# Top_Sheet.net
KiCad netlist of a schematic drawn in Altium Designer
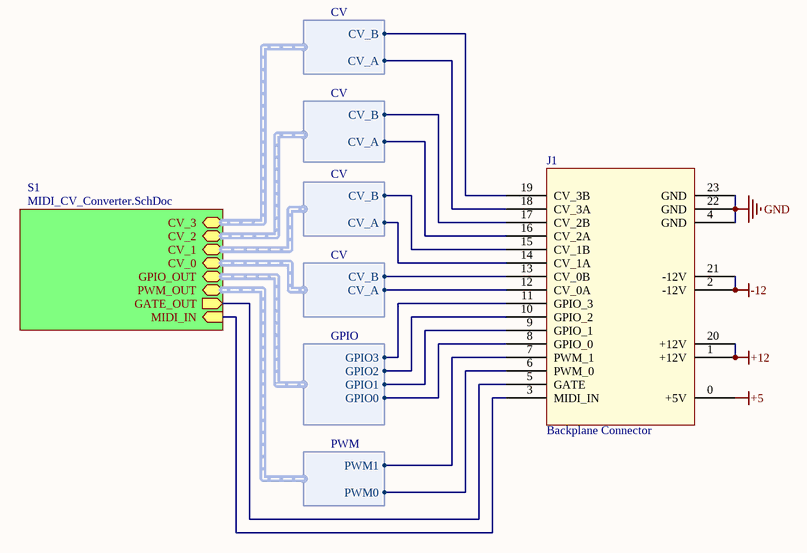
[diagram p0: Top Sheet.SchDoc]

(export (version "E")
  (design (tool "Eeschema 10.0.6"))
  (components
    (comp (ref "J1")
      (value "Backplane Connector")
      (footprint "MIDI-CV CONVERTER MODULE")
      (libsource (lib "Gary_Module") (part "MIDI_CV_Converter"))
    )
  )
  (nets
    (net (code "4") (name "+5") (class "Default")
      (node (ref "J1") (pin "0") (pinfunction "+5V_0") (pintype "passive"))
    )
    (net (code "5") (name "+12") (class "Default")
      (node (ref "J1") (pin "1") (pinfunction "+12V_1") (pintype "passive"))
      (node (ref "J1") (pin "20") (pinfunction "+12V_20") (pintype "passive"))
    )
    (net (code "6") (name "-12") (class "Default")
      (node (ref "J1") (pin "2") (pinfunction "-12V_2") (pintype "passive"))
      (node (ref "J1") (pin "21") (pinfunction "-12V_21") (pintype "passive"))
    )
    (net (code "7") (name "/GATE_OUT") (class "Default")
      (node (ref "J1") (pin "5") (pinfunction "GATE_5") (pintype "passive"))
    )
    (net (code "8") (name "/GPIO0") (class "Default")
      (node (ref "J1") (pin "8") (pinfunction "GPIO_0_8") (pintype "passive"))
    )
    (net (code "9") (name "/GPIO1") (class "Default")
      (node (ref "J1") (pin "9") (pinfunction "GPIO_1_9") (pintype "passive"))
    )
    (net (code "10") (name "/GPIO2") (class "Default")
      (node (ref "J1") (pin "10") (pinfunction "GPIO_2_10") (pintype "passive"))
    )
    (net (code "11") (name "/GPIO3") (class "Default")
      (node (ref "J1") (pin "11") (pinfunction "GPIO_3_11") (pintype "passive"))
    )
    (net (code "12") (name "/MIDI_IN") (class "Default")
      (node (ref "J1") (pin "3") (pinfunction "MIDI_IN_3") (pintype "passive"))
    )
    (net (code "13") (name "/PWM0") (class "Default")
      (node (ref "J1") (pin "6") (pinfunction "PWM_0_6") (pintype "passive"))
    )
    (net (code "14") (name "/PWM1") (class "Default")
      (node (ref "J1") (pin "7") (pinfunction "PWM_1_7") (pintype "passive"))
    )
    (net (code "18") (name "GND") (class "Default")
      (node (ref "J1") (pin "22") (pinfunction "GND_22") (pintype "passive"))
      (node (ref "J1") (pin "23") (pinfunction "GND_23") (pintype "passive"))
      (node (ref "J1") (pin "4") (pinfunction "GND_4") (pintype "passive"))
    )
    (net (code "19") (name "unconnected-(J1-CV_0A-Pad12)") (class "Default")
      (node (ref "J1") (pin "12") (pinfunction "CV_0A_12") (pintype "passive"))
    )
    (net (code "20") (name "unconnected-(J1-CV_0B-Pad13)") (class "Default")
      (node (ref "J1") (pin "13") (pinfunction "CV_0B_13") (pintype "passive"))
    )
    (net (code "21") (name "unconnected-(J1-CV_1A-Pad14)") (class "Default")
      (node (ref "J1") (pin "14") (pinfunction "CV_1A_14") (pintype "passive"))
    )
    (net (code "22") (name "unconnected-(J1-CV_1B-Pad15)") (class "Default")
      (node (ref "J1") (pin "15") (pinfunction "CV_1B_15") (pintype "passive"))
    )
    (net (code "23") (name "unconnected-(J1-CV_2A-Pad16)") (class "Default")
      (node (ref "J1") (pin "16") (pinfunction "CV_2A_16") (pintype "passive"))
    )
    (net (code "24") (name "unconnected-(J1-CV_2B-Pad17)") (class "Default")
      (node (ref "J1") (pin "17") (pinfunction "CV_2B_17") (pintype "passive"))
    )
    (net (code "25") (name "unconnected-(J1-CV_3A-Pad18)") (class "Default")
      (node (ref "J1") (pin "18") (pinfunction "CV_3A_18") (pintype "passive"))
    )
    (net (code "26") (name "unconnected-(J1-CV_3B-Pad19)") (class "Default")
      (node (ref "J1") (pin "19") (pinfunction "CV_3B_19") (pintype "passive"))
    )
  )
)
